# cdh.net
KiCad netlist of a schematic drawn in Altium Designer
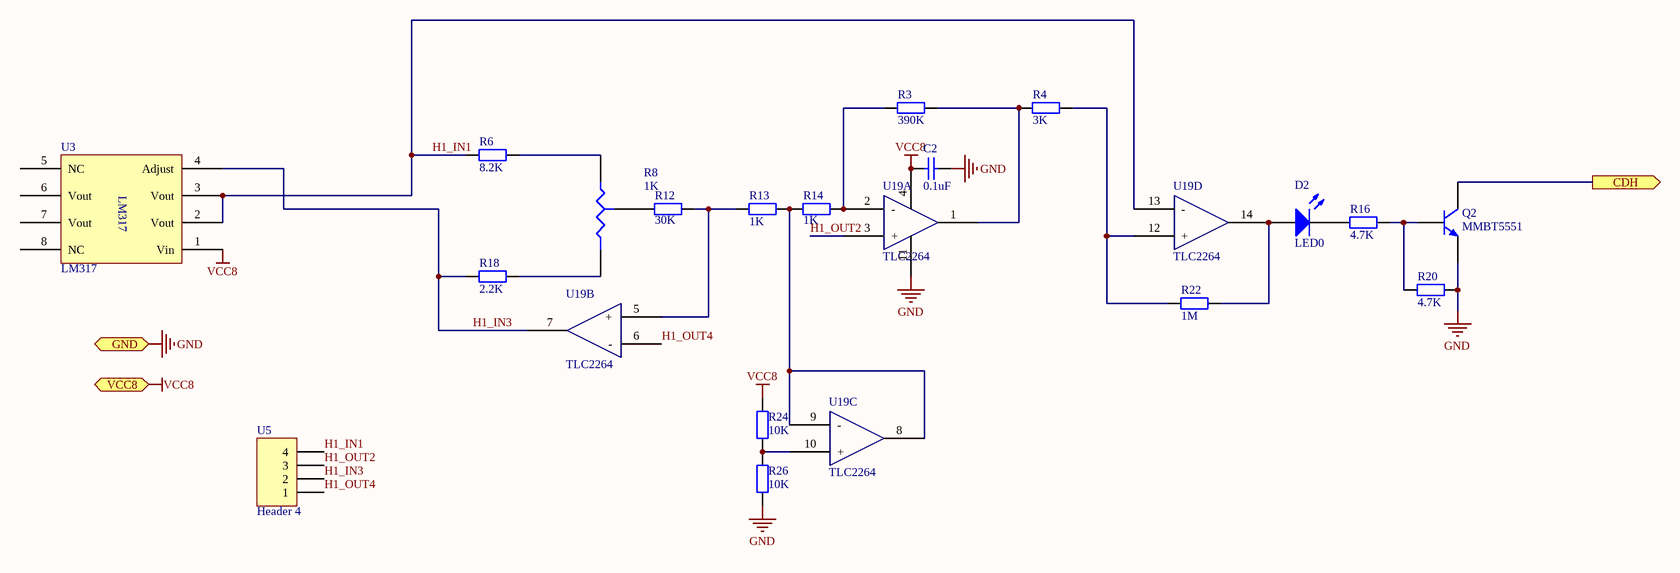
[diagram p0: cdh.SchDoc]

(export (version "E")
  (design (tool "Eeschema 10.0.6"))
  (components
    (comp (ref "C2")
      (value "0.1uF")
      (footprint "C0805")
      (description "Capacitor (Semiconductor SIM Model)")
      (fields (field (name "PUBLISHER") "Altium Limited"))
      (libsource (lib "Miscellaneous Devices") (part "Cap Semi"))
    )
    (comp (ref "D2")
      (value "LED0")
      (footprint "LED1")
      (description "Typical INFRARED GaAs LED")
      (fields (field (name "PUBLISHER") "Altium Limited"))
      (libsource (lib "Miscellaneous Devices") (part "LED0"))
    )
    (comp (ref "Q2")
      (value "MMBT5551")
      (footprint "SOT-23")
      (description "NPN Bipolar Transistor")
      (fields (field (name "PUBLISHER") "Altium Limited"))
      (libsource (lib "Miscellaneous Devices") (part "NPN"))
    )
    (comp (ref "R3")
      (value "390K")
      (footprint "0805")
      (description "Resistor")
      (fields (field (name "PUBLISHER") "Altium Limited"))
      (libsource (lib "Miscellaneous Devices") (part "Res2"))
    )
    (comp (ref "R4")
      (value "3K")
      (footprint "0805")
      (description "Resistor")
      (fields (field (name "PUBLISHER") "Altium Limited"))
      (libsource (lib "Miscellaneous Devices") (part "Res2"))
    )
    (comp (ref "R6")
      (value "8.2K")
      (footprint "0805")
      (description "Resistor")
      (fields (field (name "PUBLISHER") "Altium Limited"))
      (libsource (lib "Miscellaneous Devices") (part "Res2"))
    )
    (comp (ref "R8")
      (value "1K")
      (footprint "3224W")
      (description "Tapped Resistor")
      (fields (field (name "Comment") "Res Tap") (field (name "PUBLISHER") "Altium Limited"))
      (libsource (lib "Miscellaneous Devices") (part "Res Tap"))
    )
    (comp (ref "R12")
      (value "30K")
      (footprint "0805")
      (description "Resistor")
      (fields (field (name "PUBLISHER") "Altium Limited"))
      (libsource (lib "Miscellaneous Devices") (part "Res2"))
    )
    (comp (ref "R13")
      (value "1K")
      (footprint "0805")
      (description "Resistor")
      (fields (field (name "PUBLISHER") "Altium Limited"))
      (libsource (lib "Miscellaneous Devices") (part "Res2"))
    )
    (comp (ref "R14")
      (value "1K")
      (footprint "0805")
      (description "Resistor")
      (fields (field (name "PUBLISHER") "Altium Limited"))
      (libsource (lib "") (part "Res2_1"))
    )
    (comp (ref "R16")
      (value "4.7K")
      (footprint "0603")
      (description "Resistor")
      (fields (field (name "PUBLISHER") "Altium Limited"))
      (libsource (lib "Miscellaneous Devices") (part "Res2"))
    )
    (comp (ref "R18")
      (value "2.2K")
      (footprint "0805")
      (description "Resistor")
      (fields (field (name "PUBLISHER") "Altium Limited"))
      (libsource (lib "Miscellaneous Devices") (part "Res2"))
    )
    (comp (ref "R20")
      (value "4.7K")
      (footprint "0603")
      (description "Resistor")
      (fields (field (name "PUBLISHER") "Altium Limited"))
      (libsource (lib "Miscellaneous Devices") (part "Res2"))
    )
    (comp (ref "R22")
      (value "1M")
      (footprint "0805")
      (description "Resistor")
      (fields (field (name "PUBLISHER") "Altium Limited"))
      (libsource (lib "Miscellaneous Devices") (part "Res2"))
    )
    (comp (ref "R24")
      (value "10K")
      (footprint "0805")
      (description "Resistor")
      (fields (field (name "PUBLISHER") "Altium Limited"))
      (libsource (lib "") (part "Res2_2"))
    )
    (comp (ref "R26")
      (value "10K")
      (footprint "0805")
      (description "Resistor")
      (fields (field (name "PUBLISHER") "Altium Limited"))
      (libsource (lib "") (part "Res2_2"))
    )
    (comp (ref "U3") (value "LM317") (footprint "SO-8") (libsource (lib "磁导航") (part "LM317")))
    (comp (ref "U5")
      (value "Header 4")
      (footprint "PIN4")
      (description "Header, 4-Pin")
      (fields (field (name "PUBLISHER") "Altium Limited"))
      (libsource (lib "Miscellaneous Connectors") (part "Header 4"))
    )
    (comp (ref "U19") (value "TLC2264") (footprint "TSSOP14") (libsource (lib "EXPLORER") (part "TLC2264")))
  )
  (nets
    (net (code "1") (name "/CDH") (class "Default")
      (node (ref "Q2") (pin "1") (pinfunction "C_1") (pintype "passive"))
    )
    (net (code "2") (name "/H1_IN1") (class "Default")
      (node (ref "R6") (pin "1") (pinfunction "1_1") (pintype "passive"))
      (node (ref "U19") (pin "13") (pinfunction "-_13") (pintype "passive"))
      (node (ref "U3") (pin "2") (pinfunction "Vout_2") (pintype "passive"))
      (node (ref "U3") (pin "3") (pinfunction "Vout_3") (pintype "passive"))
      (node (ref "U5") (pin "4") (pinfunction "4_4") (pintype "passive"))
    )
    (net (code "3") (name "/H1_IN3") (class "Default")
      (node (ref "R18") (pin "1") (pinfunction "1_1") (pintype "passive"))
      (node (ref "U19") (pin "7") (pinfunction "2OUT_7") (pintype "passive"))
      (node (ref "U3") (pin "4") (pinfunction "Adjust_4") (pintype "passive"))
      (node (ref "U5") (pin "2") (pinfunction "2_2") (pintype "passive"))
    )
    (net (code "4") (name "/H1_OUT2") (class "Default")
      (node (ref "U19") (pin "3") (pinfunction "+_3") (pintype "passive"))
      (node (ref "U5") (pin "3") (pinfunction "3_3") (pintype "passive"))
    )
    (net (code "5") (name "/H1_OUT4") (class "Default")
      (node (ref "U19") (pin "6") (pinfunction "-_6") (pintype "passive"))
      (node (ref "U5") (pin "1") (pinfunction "1_1") (pintype "passive"))
    )
    (net (code "6") (name "GND") (class "Default")
      (node (ref "C2") (pin "1") (pinfunction "1_1") (pintype "passive"))
      (node (ref "Q2") (pin "3") (pinfunction "E_3") (pintype "passive"))
      (node (ref "R20") (pin "2") (pinfunction "2_2") (pintype "passive"))
      (node (ref "R26") (pin "1") (pinfunction "1_1") (pintype "passive"))
      (node (ref "U19") (pin "11") (pinfunction "GND_11") (pintype "passive"))
    )
    (net (code "7") (name "Net-(D2-A)") (class "Default")
      (node (ref "D2") (pin "1") (pinfunction "A_1") (pintype "passive"))
      (node (ref "R22") (pin "2") (pinfunction "2_2") (pintype "passive"))
      (node (ref "U19") (pin "14") (pinfunction "4OUT_14") (pintype "passive"))
    )
    (net (code "8") (name "Net-(D2-K)") (class "Default")
      (node (ref "D2") (pin "2") (pinfunction "K_2") (pintype "passive"))
      (node (ref "R16") (pin "1") (pinfunction "1_1") (pintype "passive"))
    )
    (net (code "9") (name "Net-(Q2-B)") (class "Default")
      (node (ref "Q2") (pin "2") (pinfunction "B_2") (pintype "passive"))
      (node (ref "R16") (pin "2") (pinfunction "2_2") (pintype "passive"))
      (node (ref "R20") (pin "1") (pinfunction "1_1") (pintype "passive"))
    )
    (net (code "10") (name "Net-(R8-A)") (class "Default")
      (node (ref "R6") (pin "2") (pinfunction "2_2") (pintype "passive"))
      (node (ref "R8") (pin "1") (pinfunction "A_1") (pintype "passive"))
    )
    (net (code "11") (name "Net-(R8-B)") (class "Default")
      (node (ref "R18") (pin "2") (pinfunction "2_2") (pintype "passive"))
      (node (ref "R8") (pin "2") (pinfunction "B_2") (pintype "passive"))
    )
    (net (code "12") (name "Net-(R8-TAP)") (class "Default")
      (node (ref "R12") (pin "1") (pinfunction "1_1") (pintype "passive"))
      (node (ref "R8") (pin "3") (pinfunction "TAP_3") (pintype "passive"))
    )
    (net (code "13") (name "Net-(U19A--)") (class "Default")
      (node (ref "R14") (pin "1") (pinfunction "1_1") (pintype "passive"))
      (node (ref "R3") (pin "1") (pinfunction "1_1") (pintype "passive"))
      (node (ref "U19") (pin "2") (pinfunction "-_2") (pintype "passive"))
    )
    (net (code "14") (name "Net-(U19A-1OUT)") (class "Default")
      (node (ref "R3") (pin "2") (pinfunction "2_2") (pintype "passive"))
      (node (ref "R4") (pin "1") (pinfunction "1_1") (pintype "passive"))
      (node (ref "U19") (pin "1") (pinfunction "1OUT_1") (pintype "passive"))
    )
    (net (code "15") (name "Net-(U19B-+)") (class "Default")
      (node (ref "R12") (pin "2") (pinfunction "2_2") (pintype "passive"))
      (node (ref "R13") (pin "1") (pinfunction "1_1") (pintype "passive"))
      (node (ref "U19") (pin "5") (pinfunction "+_5") (pintype "passive"))
    )
    (net (code "16") (name "Net-(U19C-+)") (class "Default")
      (node (ref "R24") (pin "1") (pinfunction "1_1") (pintype "passive"))
      (node (ref "R26") (pin "2") (pinfunction "2_2") (pintype "passive"))
      (node (ref "U19") (pin "10") (pinfunction "+_10") (pintype "passive"))
    )
    (net (code "17") (name "Net-(U19C--)") (class "Default")
      (node (ref "R13") (pin "2") (pinfunction "2_2") (pintype "passive"))
      (node (ref "R14") (pin "2") (pinfunction "2_2") (pintype "passive"))
      (node (ref "U19") (pin "8") (pinfunction "3OUT_8") (pintype "passive"))
      (node (ref "U19") (pin "9") (pinfunction "-_9") (pintype "passive"))
    )
    (net (code "18") (name "Net-(U19D-+)") (class "Default")
      (node (ref "R22") (pin "1") (pinfunction "1_1") (pintype "passive"))
      (node (ref "R4") (pin "2") (pinfunction "2_2") (pintype "passive"))
      (node (ref "U19") (pin "12") (pinfunction "+_12") (pintype "passive"))
    )
    (net (code "19") (name "VCC8") (class "Default")
      (node (ref "C2") (pin "2") (pinfunction "2_2") (pintype "passive"))
      (node (ref "R24") (pin "2") (pinfunction "2_2") (pintype "passive"))
      (node (ref "U19") (pin "4") (pinfunction "VCC_4") (pintype "passive"))
      (node (ref "U3") (pin "1") (pinfunction "Vin_1") (pintype "passive"))
    )
    (net (code "20") (name "unconnected-(U3-NC-Pad5)") (class "Default")
      (node (ref "U3") (pin "5") (pinfunction "NC_5") (pintype "passive"))
    )
    (net (code "21") (name "unconnected-(U3-NC-Pad8)") (class "Default")
      (node (ref "U3") (pin "8") (pinfunction "NC_8") (pintype "passive"))
    )
    (net (code "22") (name "unconnected-(U3-Vout-Pad6)") (class "Default")
      (node (ref "U3") (pin "6") (pinfunction "Vout_6") (pintype "passive"))
    )
    (net (code "23") (name "unconnected-(U3-Vout-Pad7)") (class "Default")
      (node (ref "U3") (pin "7") (pinfunction "Vout_7") (pintype "passive"))
    )
  )
)
